# RS485_CAN-V1.net
KiCad netlist of a schematic drawn in Altium Designer
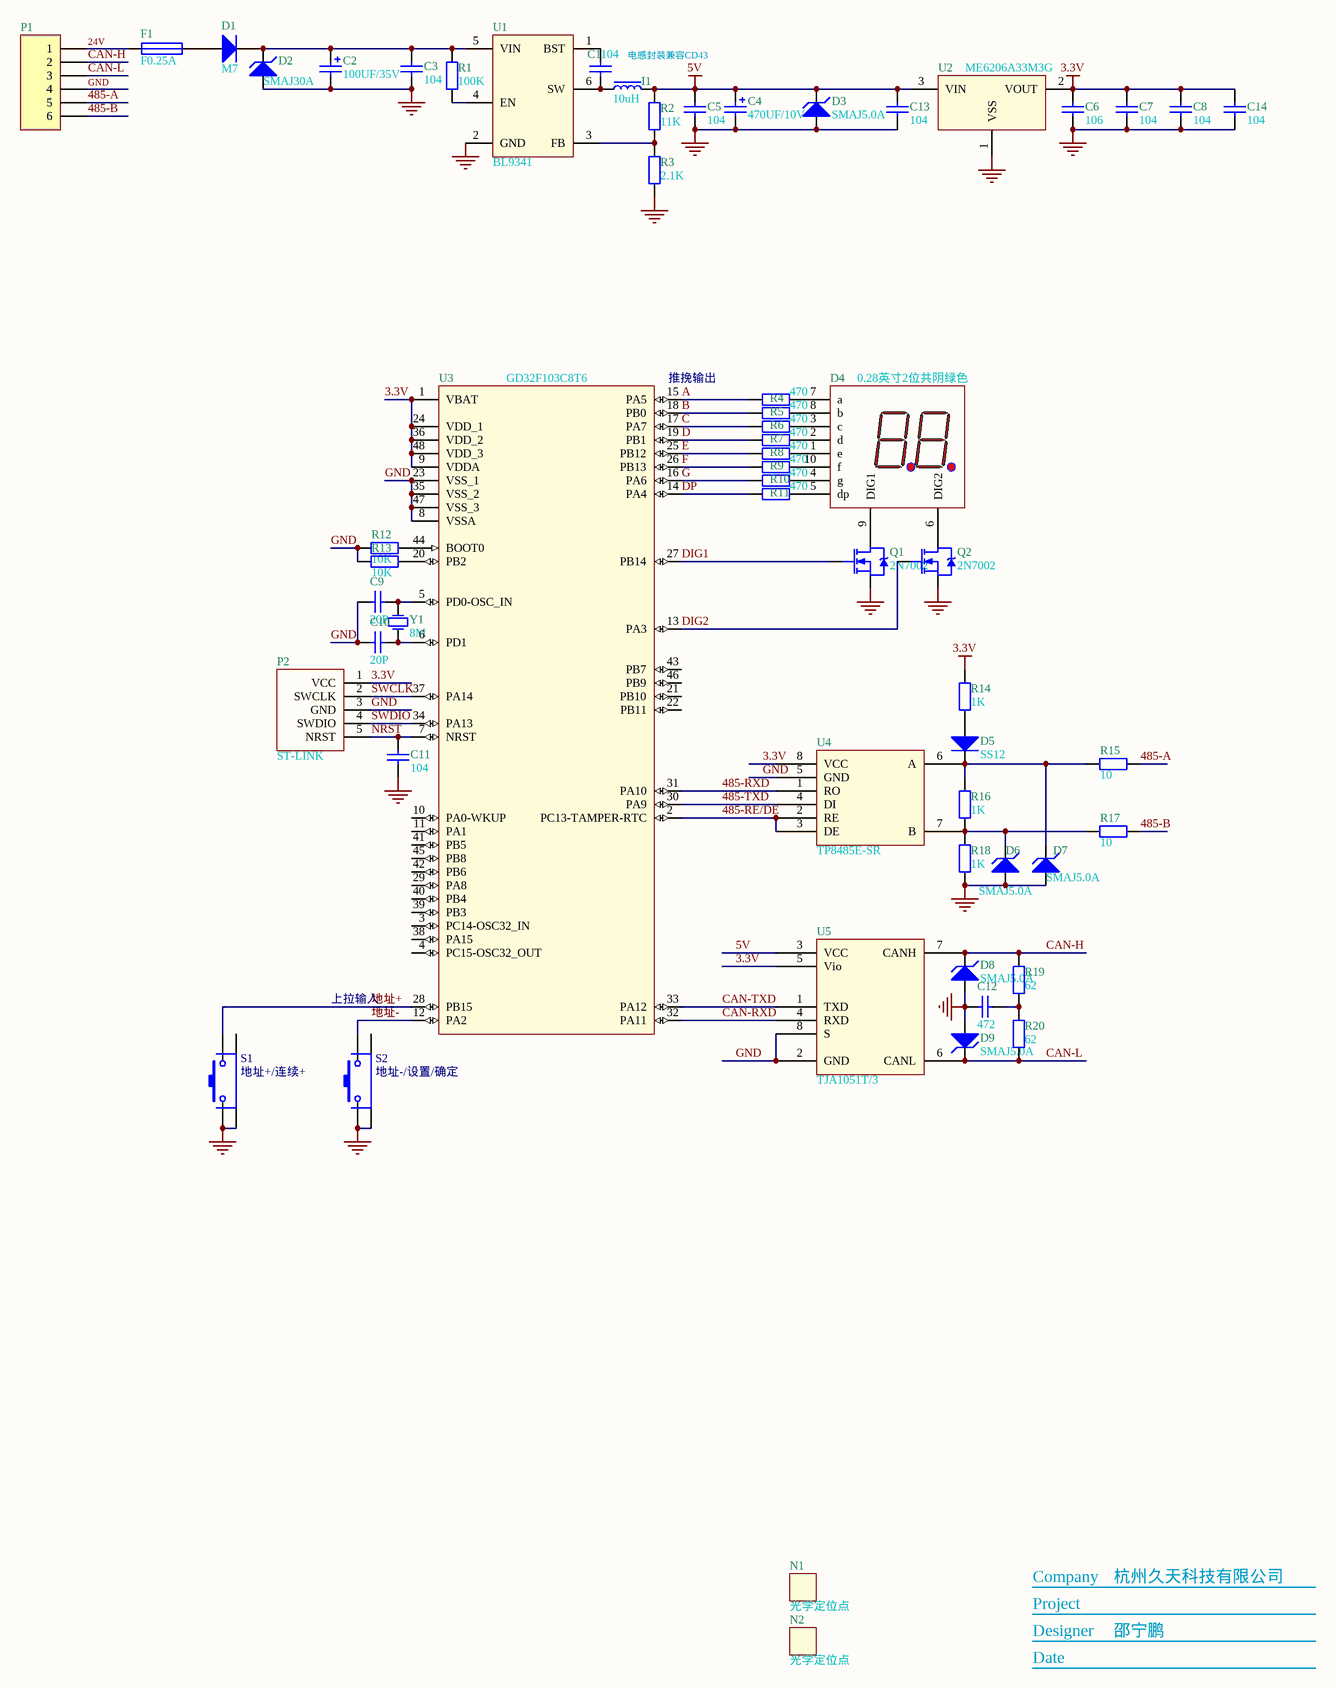
[diagram p0: RS485转CAN-V1.SchDoc]

(export (version "E")
  (design (tool "Eeschema 10.0.6"))
  (components
    (comp (ref "C1")
      (value "104")
      (footprint "C-0603")
      (description "Capacitor")
      (fields (field (name "PUBLISHER") "Altium Limited"))
      (libsource (lib "元件2.0") (part "Cap"))
    )
    (comp (ref "C2")
      (value "100UF/35V")
      (footprint "贴片固态电容6.3*7.7")
      (description "Polarized Capacitor (Radial)")
      (fields (field (name "PUBLISHER") "Altium Limited"))
      (libsource (lib "元件2.0") (part "Cap Pol1"))
    )
    (comp (ref "C3")
      (value "104")
      (footprint "C-0603")
      (description "Capacitor")
      (fields (field (name "PUBLISHER") "Altium Limited"))
      (libsource (lib "元件2.0") (part "Cap"))
    )
    (comp (ref "C4")
      (value "470UF/10V")
      (footprint "贴片固态电容6.3*7.7")
      (description "Polarized Capacitor (Radial)")
      (fields (field (name "PUBLISHER") "Altium Limited"))
      (libsource (lib "元件2.0") (part "Cap Pol1"))
    )
    (comp (ref "C5")
      (value "104")
      (footprint "C-0603")
      (description "Capacitor")
      (fields (field (name "PUBLISHER") "Altium Limited"))
      (libsource (lib "元件2.0") (part "Cap"))
    )
    (comp (ref "C6")
      (value "106")
      (footprint "C-0603")
      (description "Capacitor")
      (fields (field (name "PUBLISHER") "Altium Limited"))
      (libsource (lib "元件2.0") (part "Cap"))
    )
    (comp (ref "C7")
      (value "104")
      (footprint "C-0603")
      (description "Capacitor")
      (fields (field (name "PUBLISHER") "Altium Limited"))
      (libsource (lib "元件2.0") (part "Cap"))
    )
    (comp (ref "C8")
      (value "104")
      (footprint "C-0603")
      (description "Capacitor")
      (fields (field (name "PUBLISHER") "Altium Limited"))
      (libsource (lib "元件2.0") (part "Cap"))
    )
    (comp (ref "C9")
      (value "20P")
      (footprint "C-0603")
      (description "0805")
      (fields (field (name "PUBLISHER") "Altium Limited"))
      (libsource (lib "2电容-V1.0") (part "Cap-0603"))
    )
    (comp (ref "C10")
      (value "20P")
      (footprint "C-0603")
      (description "0805")
      (fields (field (name "PUBLISHER") "Altium Limited"))
      (libsource (lib "2电容-V1.0") (part "Cap-0603"))
    )
    (comp (ref "C11")
      (value "104")
      (footprint "C-0603")
      (description "0805")
      (fields (field (name "PUBLISHER") "Altium Limited"))
      (libsource (lib "2电容-V1.0") (part "Cap-0603"))
    )
    (comp (ref "C12")
      (value "472")
      (footprint "C-0603")
      (description "0805")
      (fields (field (name "PUBLISHER") "Altium Limited"))
      (libsource (lib "2电容-V1.0") (part "Cap-0603"))
    )
    (comp (ref "C13")
      (value "104")
      (footprint "C-0603")
      (description "Capacitor")
      (fields (field (name "PUBLISHER") "Altium Limited"))
      (libsource (lib "元件2.0") (part "Cap"))
    )
    (comp (ref "C14")
      (value "104")
      (footprint "C-0603")
      (description "Capacitor")
      (fields (field (name "PUBLISHER") "Altium Limited"))
      (libsource (lib "元件2.0") (part "Cap"))
    )
    (comp (ref "D1")
      (value "M7")
      (footprint "SMA")
      (description "SMA")
      (fields (field (name "PUBLISHER") "Altium Limited"))
      (libsource (lib "4二极管-V1.1") (part "M7"))
    )
    (comp (ref "D2")
      (value "SMAJ30A")
      (footprint "SMA")
      (description "SMB")
      (libsource (lib "4二极管-V1.1") (part "TVS-1"))
    )
    (comp (ref "D3")
      (value "SMAJ5.0A")
      (footprint "SMA")
      (description "SMB")
      (libsource (lib "4二极管-V1.1") (part "TVS-1"))
    )
    (comp (ref "D4")
      (value "0.28英寸2位共阴绿色")
      (footprint "2位0.28英寸")
      (libsource (lib "7显示屏-V1.0") (part "2位数码管"))
    )
    (comp (ref "D5")
      (value "SS12")
      (footprint "SMA")
      (description "SMA")
      (libsource (lib "4二极管-V1.1") (part "SS14"))
    )
    (comp (ref "D6")
      (value "SMAJ5.0A")
      (footprint "SMA")
      (description "SMB")
      (libsource (lib "4二极管-V1.1") (part "TVS-1"))
    )
    (comp (ref "D7")
      (value "SMAJ5.0A")
      (footprint "SMA")
      (description "SMB")
      (libsource (lib "4二极管-V1.1") (part "TVS-1"))
    )
    (comp (ref "D8")
      (value "SMAJ5.0A")
      (footprint "SMA")
      (description "SMB")
      (libsource (lib "4二极管-V1.1") (part "TVS-1"))
    )
    (comp (ref "D9")
      (value "SMAJ5.0A")
      (footprint "SMA")
      (description "SMB")
      (libsource (lib "4二极管-V1.1") (part "TVS-1"))
    )
    (comp (ref "F1")
      (value "F0.25A")
      (footprint "FUSE-3*10带引线")
      (description "Fuse")
      (fields (field (name "PUBLISHER") "Altium Limited"))
      (libsource (lib "11其他元件-V1.0") (part "Fuse 1"))
    )
    (comp (ref "I1") (value "10uH") (footprint "4030") (libsource (lib "3电感-V1.0") (part "Inductance3")))
    (comp (ref "N1") (value "光学定位点") (footprint "MARK-1mm-3mm") (libsource (lib "11其他元件-V1.0") (part "无引脚")))
    (comp (ref "N2") (value "光学定位点") (footprint "MARK-1mm-3mm") (libsource (lib "11其他元件-V1.0") (part "无引脚")))
    (comp (ref "P1")
      (value "~")
      (footprint "KF2EDGVC-5.08-6P")
      (description "Header, 6-Pin")
      (fields (field (name "PUBLISHER") "Altium Limited"))
      (libsource (lib "5排针-V1.0") (part "Header 6"))
    )
    (comp (ref "P2") (value "ST-LINK") (footprint "5P下载口") (libsource (lib "下载口") (part "ST-LINK-STM32")))
    (comp (ref "Q1") (value "2N7002") (footprint "SOT-23") (libsource (lib "4二极管-V1.1") (part "2N7002")))
    (comp (ref "Q2") (value "2N7002") (footprint "SOT-23") (libsource (lib "4二极管-V1.1") (part "2N7002")))
    (comp (ref "R1")
      (value "100K")
      (footprint "R-0603")
      (description "0603")
      (fields (field (name "PUBLISHER") "Altium Limited"))
      (libsource (lib "") (part "Res2-0603_1"))
    )
    (comp (ref "R2")
      (value "11K")
      (footprint "R-0603")
      (description "0603")
      (fields (field (name "PUBLISHER") "Altium Limited"))
      (libsource (lib "") (part "Res2-0603_1"))
    )
    (comp (ref "R3")
      (value "2.1K")
      (footprint "R-0603")
      (description "0603")
      (fields (field (name "PUBLISHER") "Altium Limited"))
      (libsource (lib "") (part "Res2-0603_1"))
    )
    (comp (ref "R4")
      (value "470")
      (footprint "R-0603")
      (description "0603")
      (fields (field (name "PUBLISHER") "Altium Limited"))
      (libsource (lib "1电阻-V1.0") (part "Res2-0603"))
    )
    (comp (ref "R5")
      (value "470")
      (footprint "R-0603")
      (description "0603")
      (fields (field (name "PUBLISHER") "Altium Limited"))
      (libsource (lib "1电阻-V1.0") (part "Res2-0603"))
    )
    (comp (ref "R6")
      (value "470")
      (footprint "R-0603")
      (description "0603")
      (fields (field (name "PUBLISHER") "Altium Limited"))
      (libsource (lib "1电阻-V1.0") (part "Res2-0603"))
    )
    (comp (ref "R7")
      (value "470")
      (footprint "R-0603")
      (description "0603")
      (fields (field (name "PUBLISHER") "Altium Limited"))
      (libsource (lib "1电阻-V1.0") (part "Res2-0603"))
    )
    (comp (ref "R8")
      (value "470")
      (footprint "R-0603")
      (description "0603")
      (fields (field (name "PUBLISHER") "Altium Limited"))
      (libsource (lib "1电阻-V1.0") (part "Res2-0603"))
    )
    (comp (ref "R9")
      (value "470")
      (footprint "R-0603")
      (description "0603")
      (fields (field (name "PUBLISHER") "Altium Limited"))
      (libsource (lib "1电阻-V1.0") (part "Res2-0603"))
    )
    (comp (ref "R10")
      (value "470")
      (footprint "R-0603")
      (description "0603")
      (fields (field (name "PUBLISHER") "Altium Limited"))
      (libsource (lib "1电阻-V1.0") (part "Res2-0603"))
    )
    (comp (ref "R11")
      (value "470")
      (footprint "R-0603")
      (description "0603")
      (fields (field (name "PUBLISHER") "Altium Limited"))
      (libsource (lib "1电阻-V1.0") (part "Res2-0603"))
    )
    (comp (ref "R12")
      (value "10K")
      (footprint "R-0603")
      (description "0603")
      (fields (field (name "PUBLISHER") "Altium Limited"))
      (libsource (lib "") (part "Res2-0603_1"))
    )
    (comp (ref "R13")
      (value "10K")
      (footprint "R-0603")
      (description "0603")
      (fields (field (name "PUBLISHER") "Altium Limited"))
      (libsource (lib "") (part "Res2-0603_1"))
    )
    (comp (ref "R14")
      (value "1K")
      (footprint "R-0603")
      (description "Resistor")
      (fields (field (name "PUBLISHER") "Altium Limited"))
      (libsource (lib "元件2.0") (part "Res2"))
    )
    (comp (ref "R15")
      (value "10")
      (footprint "R-0603")
      (description "Resistor")
      (fields (field (name "PUBLISHER") "Altium Limited"))
      (libsource (lib "Miscellaneous Devices") (part "Res2"))
    )
    (comp (ref "R16")
      (value "1K")
      (footprint "R-1206")
      (description "Resistor")
      (fields (field (name "PUBLISHER") "Altium Limited"))
      (libsource (lib "") (part "Res2_1"))
    )
    (comp (ref "R17")
      (value "10")
      (footprint "R-0603")
      (description "Resistor")
      (fields (field (name "PUBLISHER") "Altium Limited"))
      (libsource (lib "Miscellaneous Devices") (part "Res2"))
    )
    (comp (ref "R18")
      (value "1K")
      (footprint "R-0603")
      (description "Resistor")
      (fields (field (name "PUBLISHER") "Altium Limited"))
      (libsource (lib "") (part "Res2_1"))
    )
    (comp (ref "R19")
      (value "62")
      (footprint "R-1206")
      (description "Resistor")
      (fields (field (name "PUBLISHER") "Altium Limited"))
      (libsource (lib "") (part "Res2_1"))
    )
    (comp (ref "R20")
      (value "62")
      (footprint "R-1206")
      (description "Resistor")
      (fields (field (name "PUBLISHER") "Altium Limited"))
      (libsource (lib "") (part "Res2_1"))
    )
    (comp (ref "S1")
      (value "地址+/连续+")
      (footprint "SB-3*6*3.5")
      (description "SB-6*6*3.1")
      (fields (field (name "PUBLISHER") "Altium Limited"))
      (libsource (lib "开关-V1") (part "SB-6*6*3.1_1"))
    )
    (comp (ref "S2")
      (value "地址-/设置/确定")
      (footprint "SB-3*6*3.5")
      (description "SB-6*6*3.1")
      (fields (field (name "PUBLISHER") "Altium Limited"))
      (libsource (lib "开关-V1") (part "SB-6*6*3.1_1"))
    )
    (comp (ref "U1") (value "BL9341") (footprint "SOT-23-6-m") (libsource (lib "电源芯片DC-DC") (part "BL9341")))
    (comp (ref "U2")
      (value "ME6206A33M3G")
      (footprint "SOT-23")
      (description "LDO稳压 SOT-23")
      (libsource (lib "电源芯片-线性稳压-V1") (part "ME6206A33M3G"))
    )
    (comp (ref "U3")
      (value "GD32F103C8T6")
      (footprint "LQFP48-L")
      (libsource (lib "9单片机-V1.0") (part "GD32F103C8T6"))
    )
    (comp (ref "U4")
      (value "TP8485E-SR")
      (footprint "SOP-8-m")
      (description "RS485总线转串口")
      (libsource (lib "集成电路1.0") (part "MAX3082"))
    )
    (comp (ref "U5") (value "TJA1051T/3") (footprint "SOP-8-M") (libsource (lib "通讯-V1") (part "TJA1051T/3")))
    (comp (ref "Y1") (value "8M") (footprint "HC-49SMD") (libsource (lib "11其他元件-V1.0") (part "晶振")))
  )
  (nets
    (net (code "1") (name "/24V") (class "Default")
      (node (ref "F1") (pin "1") (pinfunction "1_1") (pintype "passive"))
      (node (ref "P1") (pin "1") (pinfunction "1_1") (pintype "passive"))
    )
    (net (code "2") (name "/485-A") (class "Default")
      (node (ref "P1") (pin "5") (pinfunction "5_5") (pintype "passive"))
      (node (ref "R15") (pin "1") (pinfunction "1_1") (pintype "passive"))
    )
    (net (code "3") (name "/485-B") (class "Default")
      (node (ref "P1") (pin "6") (pinfunction "6_6") (pintype "passive"))
      (node (ref "R17") (pin "1") (pinfunction "1_1") (pintype "passive"))
    )
    (net (code "4") (name "/485-RE{slash}DE") (class "Default")
      (node (ref "U3") (pin "2") (pinfunction "PC13-TAMPER-RTC_2") (pintype "bidirectional"))
      (node (ref "U4") (pin "2") (pinfunction "RE_2") (pintype "passive"))
      (node (ref "U4") (pin "3") (pinfunction "DE_3") (pintype "passive"))
    )
    (net (code "5") (name "/485-RXD") (class "Default")
      (node (ref "U3") (pin "31") (pinfunction "PA10_31") (pintype "bidirectional"))
      (node (ref "U4") (pin "1") (pinfunction "RO_1") (pintype "passive"))
    )
    (net (code "6") (name "/485-TXD") (class "Default")
      (node (ref "U3") (pin "30") (pinfunction "PA9_30") (pintype "bidirectional"))
      (node (ref "U4") (pin "4") (pinfunction "DI_4") (pintype "passive"))
    )
    (net (code "7") (name "/A") (class "Default")
      (node (ref "R4") (pin "1") (pinfunction "1_1") (pintype "passive"))
      (node (ref "U3") (pin "15") (pinfunction "PA5_15") (pintype "bidirectional"))
    )
    (net (code "8") (name "/B") (class "Default")
      (node (ref "R5") (pin "1") (pinfunction "1_1") (pintype "passive"))
      (node (ref "U3") (pin "18") (pinfunction "PB0_18") (pintype "bidirectional"))
    )
    (net (code "9") (name "/C") (class "Default")
      (node (ref "R6") (pin "1") (pinfunction "1_1") (pintype "passive"))
      (node (ref "U3") (pin "17") (pinfunction "PA7_17") (pintype "bidirectional"))
    )
    (net (code "10") (name "/CAN-H") (class "Default")
      (node (ref "D8") (pin "2") (pinfunction "K_2") (pintype "passive"))
      (node (ref "P1") (pin "2") (pinfunction "2_2") (pintype "passive"))
      (node (ref "R19") (pin "1") (pinfunction "1_1") (pintype "passive"))
      (node (ref "U5") (pin "7") (pinfunction "CANH_7") (pintype "passive"))
    )
    (net (code "11") (name "/CAN-L") (class "Default")
      (node (ref "D9") (pin "2") (pinfunction "K_2") (pintype "passive"))
      (node (ref "P1") (pin "3") (pinfunction "3_3") (pintype "passive"))
      (node (ref "R20") (pin "2") (pinfunction "2_2") (pintype "passive"))
      (node (ref "U5") (pin "6") (pinfunction "CANL_6") (pintype "passive"))
    )
    (net (code "12") (name "/CAN-RXD") (class "Default")
      (node (ref "U3") (pin "32") (pinfunction "PA11_32") (pintype "bidirectional"))
      (node (ref "U5") (pin "4") (pinfunction "RXD_4") (pintype "passive"))
    )
    (net (code "13") (name "/CAN-TXD") (class "Default")
      (node (ref "U3") (pin "33") (pinfunction "PA12_33") (pintype "bidirectional"))
      (node (ref "U5") (pin "1") (pinfunction "TXD_1") (pintype "passive"))
    )
    (net (code "14") (name "/D") (class "Default")
      (node (ref "R7") (pin "1") (pinfunction "1_1") (pintype "passive"))
      (node (ref "U3") (pin "19") (pinfunction "PB1_19") (pintype "bidirectional"))
    )
    (net (code "15") (name "/DIG1") (class "Default")
      (node (ref "Q1") (pin "1") (pinfunction "G_1") (pintype "passive"))
      (node (ref "U3") (pin "27") (pinfunction "PB14_27") (pintype "bidirectional"))
    )
    (net (code "16") (name "/DIG2") (class "Default")
      (node (ref "Q2") (pin "1") (pinfunction "G_1") (pintype "passive"))
      (node (ref "U3") (pin "13") (pinfunction "PA3_13") (pintype "bidirectional"))
    )
    (net (code "17") (name "/DP") (class "Default")
      (node (ref "R11") (pin "1") (pinfunction "1_1") (pintype "passive"))
      (node (ref "U3") (pin "14") (pinfunction "PA4_14") (pintype "bidirectional"))
    )
    (net (code "18") (name "/E") (class "Default")
      (node (ref "R8") (pin "1") (pinfunction "1_1") (pintype "passive"))
      (node (ref "U3") (pin "25") (pinfunction "PB12_25") (pintype "bidirectional"))
    )
    (net (code "19") (name "/F") (class "Default")
      (node (ref "R9") (pin "1") (pinfunction "1_1") (pintype "passive"))
      (node (ref "U3") (pin "26") (pinfunction "PB13_26") (pintype "bidirectional"))
    )
    (net (code "20") (name "/G") (class "Default")
      (node (ref "R10") (pin "1") (pinfunction "1_1") (pintype "passive"))
      (node (ref "U3") (pin "16") (pinfunction "PA6_16") (pintype "bidirectional"))
    )
    (net (code "21") (name "/NRST") (class "Default")
      (node (ref "C11") (pin "2") (pinfunction "2_2") (pintype "passive"))
      (node (ref "P2") (pin "5") (pinfunction "NRST_5") (pintype "passive"))
      (node (ref "U3") (pin "7") (pinfunction "NRST_7") (pintype "bidirectional"))
    )
    (net (code "22") (name "/SWCLK") (class "Default")
      (node (ref "P2") (pin "2") (pinfunction "SWCLK_2") (pintype "passive"))
      (node (ref "U3") (pin "37") (pinfunction "PA14_37") (pintype "bidirectional"))
    )
    (net (code "23") (name "/SWDIO") (class "Default")
      (node (ref "P2") (pin "4") (pinfunction "SWDIO_4") (pintype "passive"))
      (node (ref "U3") (pin "34") (pinfunction "PA13_34") (pintype "bidirectional"))
    )
    (net (code "24") (name "/地址+") (class "Default")
      (node (ref "S1") (pin "2") (pinfunction "2_2") (pintype "passive"))
      (node (ref "U3") (pin "28") (pinfunction "PB15_28") (pintype "bidirectional"))
    )
    (net (code "25") (name "/地址-") (class "Default")
      (node (ref "S2") (pin "1") (pinfunction "1_1") (pintype "passive"))
      (node (ref "U3") (pin "12") (pinfunction "PA2_12") (pintype "bidirectional"))
    )
    (net (code "26") (name "3.3V") (class "Default")
      (node (ref "C14") (pin "2") (pinfunction "2_2") (pintype "passive"))
      (node (ref "C6") (pin "2") (pinfunction "2_2") (pintype "passive"))
      (node (ref "C7") (pin "2") (pinfunction "2_2") (pintype "passive"))
      (node (ref "C8") (pin "2") (pinfunction "2_2") (pintype "passive"))
      (node (ref "P2") (pin "1") (pinfunction "VCC_1") (pintype "passive"))
      (node (ref "R14") (pin "1") (pinfunction "1_1") (pintype "passive"))
      (node (ref "U2") (pin "2") (pinfunction "VOUT_2") (pintype "passive"))
      (node (ref "U3") (pin "1") (pinfunction "VBAT_1") (pintype "power_in"))
      (node (ref "U3") (pin "24") (pinfunction "VDD_1_24") (pintype "power_in"))
      (node (ref "U3") (pin "36") (pinfunction "VDD_2_36") (pintype "power_in"))
      (node (ref "U3") (pin "48") (pinfunction "VDD_3_48") (pintype "power_in"))
      (node (ref "U3") (pin "9") (pinfunction "VDDA_9") (pintype "power_in"))
      (node (ref "U4") (pin "8") (pinfunction "VCC_8") (pintype "passive"))
      (node (ref "U5") (pin "5") (pinfunction "Vio_5") (pintype "passive"))
    )
    (net (code "27") (name "5V") (class "Default")
      (node (ref "C13") (pin "2") (pinfunction "2_2") (pintype "passive"))
      (node (ref "C4") (pin "1") (pinfunction "1_1") (pintype "passive"))
      (node (ref "C5") (pin "2") (pinfunction "2_2") (pintype "passive"))
      (node (ref "D3") (pin "2") (pinfunction "K_2") (pintype "passive"))
      (node (ref "I1") (pin "2") (pinfunction "2_2") (pintype "passive"))
      (node (ref "R2") (pin "1") (pinfunction "1_1") (pintype "passive"))
      (node (ref "U2") (pin "3") (pinfunction "VIN_3") (pintype "passive"))
      (node (ref "U5") (pin "3") (pinfunction "VCC_3") (pintype "passive"))
    )
    (net (code "28") (name "GND") (class "Default")
      (node (ref "C10") (pin "1") (pinfunction "1_1") (pintype "passive"))
      (node (ref "C11") (pin "1") (pinfunction "1_1") (pintype "passive"))
      (node (ref "C12") (pin "1") (pinfunction "1_1") (pintype "passive"))
      (node (ref "C13") (pin "1") (pinfunction "1_1") (pintype "passive"))
      (node (ref "C14") (pin "1") (pinfunction "1_1") (pintype "passive"))
      (node (ref "C2") (pin "2") (pinfunction "2_2") (pintype "passive"))
      (node (ref "C3") (pin "1") (pinfunction "1_1") (pintype "passive"))
      (node (ref "C4") (pin "2") (pinfunction "2_2") (pintype "passive"))
      (node (ref "C5") (pin "1") (pinfunction "1_1") (pintype "passive"))
      (node (ref "C6") (pin "1") (pinfunction "1_1") (pintype "passive"))
      (node (ref "C7") (pin "1") (pinfunction "1_1") (pintype "passive"))
      (node (ref "C8") (pin "1") (pinfunction "1_1") (pintype "passive"))
      (node (ref "C9") (pin "1") (pinfunction "1_1") (pintype "passive"))
      (node (ref "D2") (pin "1") (pinfunction "A_1") (pintype "passive"))
      (node (ref "D3") (pin "1") (pinfunction "A_1") (pintype "passive"))
      (node (ref "D6") (pin "1") (pinfunction "A_1") (pintype "passive"))
      (node (ref "D7") (pin "1") (pinfunction "A_1") (pintype "passive"))
      (node (ref "D8") (pin "1") (pinfunction "A_1") (pintype "passive"))
      (node (ref "D9") (pin "1") (pinfunction "A_1") (pintype "passive"))
      (node (ref "P1") (pin "4") (pinfunction "4_4") (pintype "passive"))
      (node (ref "P2") (pin "3") (pinfunction "GND_3") (pintype "passive"))
      (node (ref "Q1") (pin "2") (pinfunction "S_2") (pintype "passive"))
      (node (ref "Q2") (pin "2") (pinfunction "S_2") (pintype "passive"))
      (node (ref "R12") (pin "2") (pinfunction "2_2") (pintype "passive"))
      (node (ref "R13") (pin "2") (pinfunction "2_2") (pintype "passive"))
      (node (ref "R18") (pin "1") (pinfunction "1_1") (pintype "passive"))
      (node (ref "R3") (pin "2") (pinfunction "2_2") (pintype "passive"))
      (node (ref "S1") (pin "1") (pinfunction "1_1") (pintype "passive"))
      (node (ref "S1") (pin "3") (pinfunction "3_3") (pintype "passive"))
      (node (ref "S2") (pin "2") (pinfunction "2_2") (pintype "passive"))
      (node (ref "S2") (pin "3") (pinfunction "3_3") (pintype "passive"))
      (node (ref "U1") (pin "2") (pinfunction "GND_2") (pintype "passive"))
      (node (ref "U2") (pin "1") (pinfunction "VSS_1") (pintype "passive"))
      (node (ref "U3") (pin "23") (pinfunction "VSS_1_23") (pintype "power_in"))
      (node (ref "U3") (pin "35") (pinfunction "VSS_2_35") (pintype "power_in"))
      (node (ref "U3") (pin "47") (pinfunction "VSS_3_47") (pintype "power_in"))
      (node (ref "U3") (pin "8") (pinfunction "VSSA_8") (pintype "power_in"))
      (node (ref "U4") (pin "5") (pinfunction "GND_5") (pintype "passive"))
      (node (ref "U5") (pin "2") (pinfunction "GND_2") (pintype "passive"))
      (node (ref "U5") (pin "8") (pinfunction "S_8") (pintype "passive"))
    )
    (net (code "29") (name "Net-(C12-Pad2)") (class "Default")
      (node (ref "C12") (pin "2") (pinfunction "2_2") (pintype "passive"))
      (node (ref "R19") (pin "2") (pinfunction "2_2") (pintype "passive"))
      (node (ref "R20") (pin "1") (pinfunction "1_1") (pintype "passive"))
    )
    (net (code "30") (name "Net-(D1-A)") (class "Default")
      (node (ref "D1") (pin "1") (pinfunction "A_1") (pintype "passive"))
      (node (ref "F1") (pin "2") (pinfunction "2_2") (pintype "passive"))
    )
    (net (code "31") (name "Net-(D1-K)") (class "Default")
      (node (ref "C2") (pin "1") (pinfunction "1_1") (pintype "passive"))
      (node (ref "C3") (pin "2") (pinfunction "2_2") (pintype "passive"))
      (node (ref "D1") (pin "2") (pinfunction "K_2") (pintype "passive"))
      (node (ref "D2") (pin "2") (pinfunction "K_2") (pintype "passive"))
      (node (ref "R1") (pin "1") (pinfunction "1_1") (pintype "passive"))
      (node (ref "U1") (pin "5") (pinfunction "VIN_5") (pintype "passive"))
    )
    (net (code "32") (name "Net-(D4-DIG1)") (class "Default")
      (node (ref "D4") (pin "9") (pinfunction "DIG1_9") (pintype "passive"))
      (node (ref "Q1") (pin "3") (pinfunction "D_3") (pintype "passive"))
    )
    (net (code "33") (name "Net-(D4-DIG2)") (class "Default")
      (node (ref "D4") (pin "6") (pinfunction "DIG2_6") (pintype "passive"))
      (node (ref "Q2") (pin "3") (pinfunction "D_3") (pintype "passive"))
    )
    (net (code "34") (name "Net-(D4-a)") (class "Default")
      (node (ref "D4") (pin "7") (pinfunction "a_7") (pintype "passive"))
      (node (ref "R4") (pin "2") (pinfunction "2_2") (pintype "passive"))
    )
    (net (code "35") (name "Net-(D4-b)") (class "Default")
      (node (ref "D4") (pin "8") (pinfunction "b_8") (pintype "passive"))
      (node (ref "R5") (pin "2") (pinfunction "2_2") (pintype "passive"))
    )
    (net (code "36") (name "Net-(D4-c)") (class "Default")
      (node (ref "D4") (pin "3") (pinfunction "c_3") (pintype "passive"))
      (node (ref "R6") (pin "2") (pinfunction "2_2") (pintype "passive"))
    )
    (net (code "37") (name "Net-(D4-d)") (class "Default")
      (node (ref "D4") (pin "2") (pinfunction "d_2") (pintype "passive"))
      (node (ref "R7") (pin "2") (pinfunction "2_2") (pintype "passive"))
    )
    (net (code "38") (name "Net-(D4-dp)") (class "Default")
      (node (ref "D4") (pin "5") (pinfunction "dp_5") (pintype "passive"))
      (node (ref "R11") (pin "2") (pinfunction "2_2") (pintype "passive"))
    )
    (net (code "39") (name "Net-(D4-e)") (class "Default")
      (node (ref "D4") (pin "1") (pinfunction "e_1") (pintype "passive"))
      (node (ref "R8") (pin "2") (pinfunction "2_2") (pintype "passive"))
    )
    (net (code "40") (name "Net-(D4-f)") (class "Default")
      (node (ref "D4") (pin "10") (pinfunction "f_10") (pintype "passive"))
      (node (ref "R9") (pin "2") (pinfunction "2_2") (pintype "passive"))
    )
    (net (code "41") (name "Net-(D4-g)") (class "Default")
      (node (ref "D4") (pin "4") (pinfunction "g_4") (pintype "passive"))
      (node (ref "R10") (pin "2") (pinfunction "2_2") (pintype "passive"))
    )
    (net (code "42") (name "Net-(D5-A)") (class "Default")
      (node (ref "D5") (pin "1") (pinfunction "A_1") (pintype "passive"))
      (node (ref "R14") (pin "2") (pinfunction "2_2") (pintype "passive"))
    )
    (net (code "43") (name "Net-(D5-K)") (class "Default")
      (node (ref "D5") (pin "2") (pinfunction "K_2") (pintype "passive"))
      (node (ref "D7") (pin "2") (pinfunction "K_2") (pintype "passive"))
      (node (ref "R15") (pin "2") (pinfunction "2_2") (pintype "passive"))
      (node (ref "R16") (pin "1") (pinfunction "1_1") (pintype "passive"))
      (node (ref "U4") (pin "6") (pinfunction "A_6") (pintype "passive"))
    )
    (net (code "44") (name "Net-(D6-K)") (class "Default")
      (node (ref "D6") (pin "2") (pinfunction "K_2") (pintype "passive"))
      (node (ref "R16") (pin "2") (pinfunction "2_2") (pintype "passive"))
      (node (ref "R17") (pin "2") (pinfunction "2_2") (pintype "passive"))
      (node (ref "R18") (pin "2") (pinfunction "2_2") (pintype "passive"))
      (node (ref "U4") (pin "7") (pinfunction "B_7") (pintype "passive"))
    )
    (net (code "45") (name "Net-(U1-BST)") (class "Default")
      (node (ref "C1") (pin "2") (pinfunction "2_2") (pintype "passive"))
      (node (ref "U1") (pin "1") (pinfunction "BST_1") (pintype "passive"))
    )
    (net (code "46") (name "Net-(U1-EN)") (class "Default")
      (node (ref "R1") (pin "2") (pinfunction "2_2") (pintype "passive"))
      (node (ref "U1") (pin "4") (pinfunction "EN_4") (pintype "passive"))
    )
    (net (code "47") (name "Net-(U1-FB)") (class "Default")
      (node (ref "R2") (pin "2") (pinfunction "2_2") (pintype "passive"))
      (node (ref "R3") (pin "1") (pinfunction "1_1") (pintype "passive"))
      (node (ref "U1") (pin "3") (pinfunction "FB_3") (pintype "passive"))
    )
    (net (code "48") (name "Net-(U1-SW)") (class "Default")
      (node (ref "C1") (pin "1") (pinfunction "1_1") (pintype "passive"))
      (node (ref "I1") (pin "1") (pinfunction "1_1") (pintype "passive"))
      (node (ref "U1") (pin "6") (pinfunction "SW_6") (pintype "passive"))
    )
    (net (code "49") (name "Net-(U3-BOOT0)") (class "Default")
      (node (ref "R12") (pin "1") (pinfunction "1_1") (pintype "passive"))
      (node (ref "U3") (pin "44") (pinfunction "BOOT0_44") (pintype "input"))
    )
    (net (code "50") (name "Net-(U3-PB2)") (class "Default")
      (node (ref "R13") (pin "1") (pinfunction "1_1") (pintype "passive"))
      (node (ref "U3") (pin "20") (pinfunction "PB2_20") (pintype "bidirectional"))
    )
    (net (code "51") (name "Net-(U3-PD0-OSC_IN)") (class "Default")
      (node (ref "C9") (pin "2") (pinfunction "2_2") (pintype "passive"))
      (node (ref "U3") (pin "5") (pinfunction "PD0-OSC_IN_5") (pintype "bidirectional"))
      (node (ref "Y1") (pin "2") (pinfunction "OSC2_2") (pintype "passive"))
    )
    (net (code "52") (name "Net-(U3-PD1)") (class "Default")
      (node (ref "C10") (pin "2") (pinfunction "2_2") (pintype "passive"))
      (node (ref "U3") (pin "6") (pinfunction "PD1_6") (pintype "bidirectional"))
      (node (ref "Y1") (pin "1") (pinfunction "OSC1_1") (pintype "passive"))
    )
    (net (code "53") (name "unconnected-(S1-Pad3)") (class "Default")
      (node (ref "S1") (pin "3") (pinfunction "3_3") (pintype "passive"))
    )
    (net (code "54") (name "unconnected-(S2-Pad3)") (class "Default")
      (node (ref "S2") (pin "3") (pinfunction "3_3") (pintype "passive"))
    )
    (net (code "55") (name "unconnected-(U3-PA0-WKUP-Pad10)") (class "Default")
      (node (ref "U3") (pin "10") (pinfunction "PA0-WKUP_10") (pintype "bidirectional"))
    )
    (net (code "56") (name "unconnected-(U3-PA1-Pad11)") (class "Default")
      (node (ref "U3") (pin "11") (pinfunction "PA1_11") (pintype "bidirectional"))
    )
    (net (code "57") (name "unconnected-(U3-PA8-Pad29)") (class "Default")
      (node (ref "U3") (pin "29") (pinfunction "PA8_29") (pintype "bidirectional"))
    )
    (net (code "58") (name "unconnected-(U3-PA15-Pad38)") (class "Default")
      (node (ref "U3") (pin "38") (pinfunction "PA15_38") (pintype "bidirectional"))
    )
    (net (code "59") (name "unconnected-(U3-PB3-Pad39)") (class "Default")
      (node (ref "U3") (pin "39") (pinfunction "PB3_39") (pintype "bidirectional"))
    )
    (net (code "60") (name "unconnected-(U3-PB4-Pad40)") (class "Default")
      (node (ref "U3") (pin "40") (pinfunction "PB4_40") (pintype "bidirectional"))
    )
    (net (code "61") (name "unconnected-(U3-PB5-Pad41)") (class "Default")
      (node (ref "U3") (pin "41") (pinfunction "PB5_41") (pintype "bidirectional"))
    )
    (net (code "62") (name "unconnected-(U3-PB6-Pad42)") (class "Default")
      (node (ref "U3") (pin "42") (pinfunction "PB6_42") (pintype "bidirectional"))
    )
    (net (code "63") (name "unconnected-(U3-PB7-Pad43)") (class "Default")
      (node (ref "U3") (pin "43") (pinfunction "PB7_43") (pintype "bidirectional"))
    )
    (net (code "64") (name "unconnected-(U3-PB8-Pad45)") (class "Default")
      (node (ref "U3") (pin "45") (pinfunction "PB8_45") (pintype "bidirectional"))
    )
    (net (code "65") (name "unconnected-(U3-PB9-Pad46)") (class "Default")
      (node (ref "U3") (pin "46") (pinfunction "PB9_46") (pintype "bidirectional"))
    )
    (net (code "66") (name "unconnected-(U3-PB10-Pad21)") (class "Default")
      (node (ref "U3") (pin "21") (pinfunction "PB10_21") (pintype "bidirectional"))
    )
    (net (code "67") (name "unconnected-(U3-PB11-Pad22)") (class "Default")
      (node (ref "U3") (pin "22") (pinfunction "PB11_22") (pintype "bidirectional"))
    )
    (net (code "68") (name "unconnected-(U3-PC14-OSC32_IN-Pad3)") (class "Default")
      (node (ref "U3") (pin "3") (pinfunction "PC14-OSC32_IN_3") (pintype "bidirectional"))
    )
    (net (code "69") (name "unconnected-(U3-PC15-OSC32_OUT-Pad4)") (class "Default")
      (node (ref "U3") (pin "4") (pinfunction "PC15-OSC32_OUT_4") (pintype "bidirectional"))
    )
  )
)
